# P-TK-05-2FC-A-MB_V1_1_-20171225.net
KiCad netlist of a schematic drawn in Altium Designer
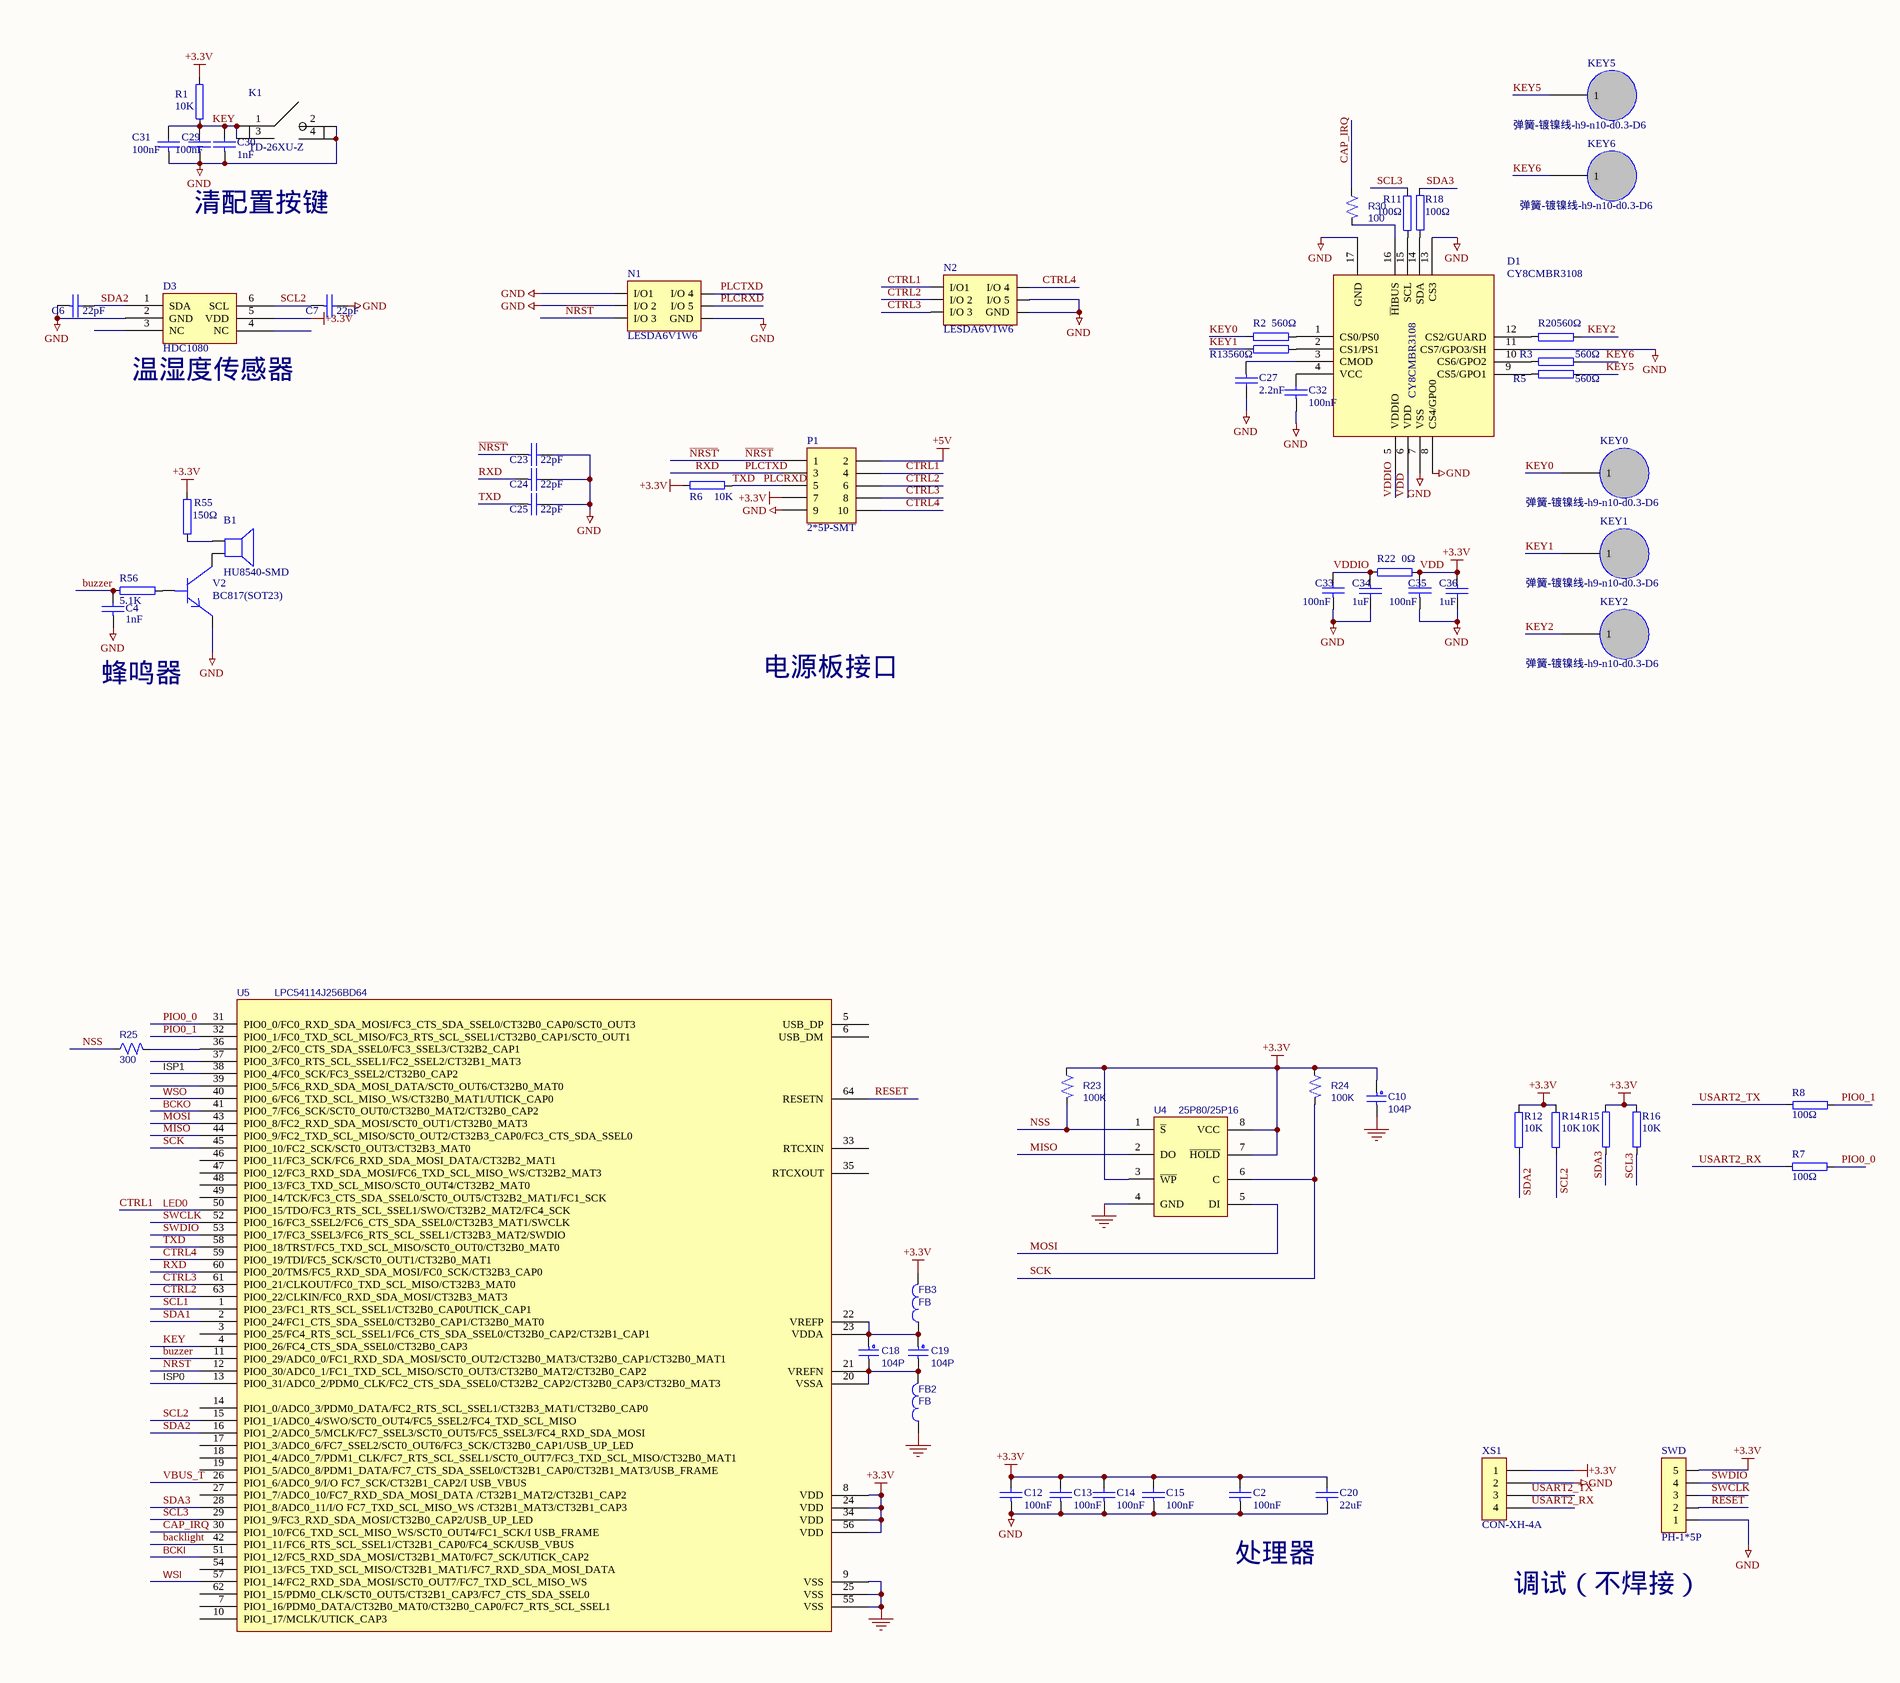
[diagram p0: P-TK-05-2FC-A-MB(V1.1)-20171225.SchDoc, left]
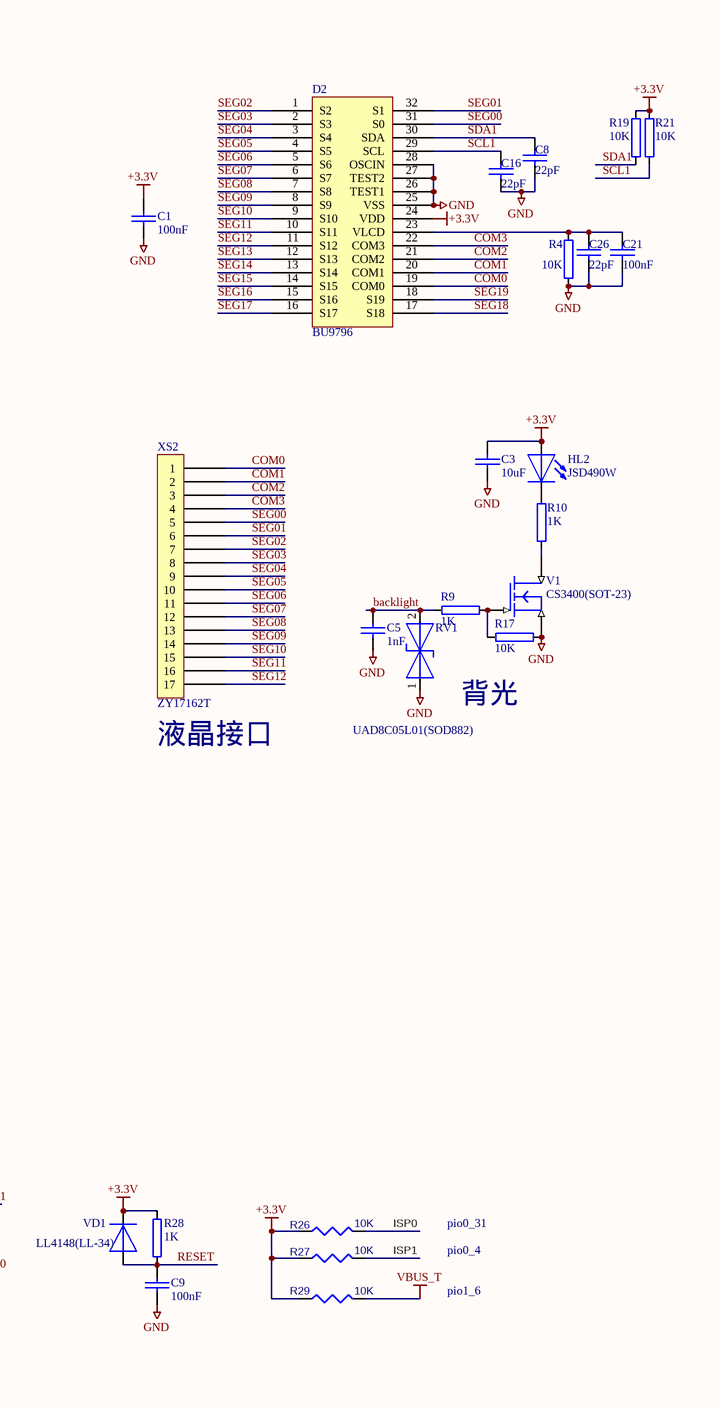
[diagram p1: P-TK-05-2FC-A-MB(V1.1)-20171225.SchDoc, right]

(export (version "E")
  (design (tool "Eeschema 10.0.6"))
  (components
    (comp (ref "B1")
      (value "HU8540-SMD")
      (footprint "HU8540")
      (description "扬声器")
      (fields (field (name "PART NUMBER") "10112020002"))
      (libsource (lib "Database_Libs1") (part "SPEAKER"))
    )
    (comp (ref "C1")
      (value "100nF")
      (footprint "C0402")
      (description "无极性电容")
      (fields (field (name "PART NUMBER") "10103020007"))
      (libsource (lib "altium-import") (part "root_1_CAP_"))
    )
    (comp (ref "C2")
      (value "100nF")
      (footprint "0603C")
      (description "无极性电容")
      (fields (field (name "PART NUMBER") "10103020007"))
      (libsource (lib "altium-import") (part "root_1_CAP_"))
    )
    (comp (ref "C3")
      (value "10uF")
      (footprint "C0603")
      (description "无极性电容")
      (fields (field (name "PART NUMBER") "10103030010"))
      (libsource (lib "altium-import") (part "root_1_CAP_"))
    )
    (comp (ref "C4")
      (value "1nF")
      (footprint "0603C")
      (description "无极性电容")
      (fields (field (name "PART NUMBER") "10103020004"))
      (libsource (lib "altium-import") (part "root_1_CAP_"))
    )
    (comp (ref "C5")
      (value "1nF")
      (footprint "0603C")
      (description "无极性电容")
      (fields (field (name "PART NUMBER") "10103020004"))
      (libsource (lib "altium-import") (part "root_1_CAP_"))
    )
    (comp (ref "C6")
      (value "22pF")
      (footprint "C0603")
      (description "无极性电容")
      (fields (field (name "PART NUMBER") "10103030023"))
      (libsource (lib "altium-import") (part "root_0_CAP_"))
    )
    (comp (ref "C7")
      (value "22pF")
      (footprint "C0603")
      (description "无极性电容")
      (fields (field (name "PART NUMBER") "10103030023"))
      (libsource (lib "altium-import") (part "root_0_CAP_"))
    )
    (comp (ref "C8")
      (value "22pF")
      (footprint "C0603")
      (description "无极性电容")
      (fields (field (name "PART NUMBER") "10103030023"))
      (libsource (lib "altium-import") (part "root_1_CAP_"))
    )
    (comp (ref "C9")
      (value "100nF")
      (footprint "0603C")
      (description "无极性电容")
      (fields (field (name "PART NUMBER") "10103020007"))
      (libsource (lib "altium-import") (part "root_1_CAP_"))
    )
    (comp (ref "C10") (value "104P") (footprint "0603C") (libsource (lib "*") (part "CAP")))
    (comp (ref "C12")
      (value "100nF")
      (footprint "0603C")
      (description "无极性电容")
      (fields (field (name "PART NUMBER") "10103020007"))
      (libsource (lib "altium-import") (part "root_1_CAP_"))
    )
    (comp (ref "C13")
      (value "100nF")
      (footprint "0603C")
      (description "无极性电容")
      (fields (field (name "PART NUMBER") "10103020007"))
      (libsource (lib "altium-import") (part "root_1_CAP_"))
    )
    (comp (ref "C14")
      (value "100nF")
      (footprint "0603C")
      (description "无极性电容")
      (fields (field (name "PART NUMBER") "10103020007"))
      (libsource (lib "altium-import") (part "root_1_CAP_"))
    )
    (comp (ref "C15")
      (value "100nF")
      (footprint "0603C")
      (description "无极性电容")
      (fields (field (name "PART NUMBER") "10103020007"))
      (libsource (lib "altium-import") (part "root_1_CAP_"))
    )
    (comp (ref "C16")
      (value "22pF")
      (footprint "C0603")
      (description "无极性电容")
      (fields (field (name "PART NUMBER") "10103030023"))
      (libsource (lib "altium-import") (part "root_1_CAP_"))
    )
    (comp (ref "C18") (value "104P") (footprint "0603C") (libsource (lib "*") (part "CAP")))
    (comp (ref "C19") (value "104P") (footprint "0603C") (libsource (lib "*") (part "CAP")))
    (comp (ref "C20")
      (value "22uF")
      (footprint "0603C")
      (description "无极性电容")
      (fields (field (name "PART NUMBER") "10103040014"))
      (libsource (lib "Database_Libs1") (part "CAP"))
    )
    (comp (ref "C21")
      (value "100nF")
      (footprint "0603C")
      (description "无极性电容")
      (fields (field (name "PART NUMBER") "10103020007"))
      (libsource (lib "altium-import") (part "root_1_CAP_"))
    )
    (comp (ref "C23")
      (value "22pF")
      (footprint "C0603")
      (description "无极性电容")
      (fields (field (name "PART NUMBER") "10103030023"))
      (libsource (lib "altium-import") (part "root_0_CAP_"))
    )
    (comp (ref "C24")
      (value "22pF")
      (footprint "C0603")
      (description "无极性电容")
      (fields (field (name "PART NUMBER") "10103030023"))
      (libsource (lib "altium-import") (part "root_0_CAP_"))
    )
    (comp (ref "C25")
      (value "22pF")
      (footprint "C0603")
      (description "无极性电容")
      (fields (field (name "PART NUMBER") "10103030023"))
      (libsource (lib "altium-import") (part "root_0_CAP_"))
    )
    (comp (ref "C26")
      (value "22pF")
      (footprint "C0603")
      (description "无极性电容")
      (fields (field (name "PART NUMBER") "10103030023"))
      (libsource (lib "altium-import") (part "root_1_CAP_"))
    )
    (comp (ref "C27")
      (value "2.2nF")
      (footprint "C0603")
      (description "无极性电容")
      (fields (field (name "PART NUMBER") "10103030025"))
      (libsource (lib "Database_Libs1") (part "CAP"))
    )
    (comp (ref "C29")
      (value "100nF")
      (footprint "0603C")
      (description "无极性电容")
      (fields (field (name "PART NUMBER") "10103020007"))
      (libsource (lib "altium-import") (part "root_1_CAP_"))
    )
    (comp (ref "C30")
      (value "1nF")
      (footprint "0603C")
      (description "无极性电容")
      (fields (field (name "PART NUMBER") "10103020004"))
      (libsource (lib "altium-import") (part "root_1_CAP_"))
    )
    (comp (ref "C31")
      (value "100nF")
      (footprint "0603C")
      (description "无极性电容")
      (fields (field (name "PART NUMBER") "10103020007"))
      (libsource (lib "altium-import") (part "root_1_CAP_"))
    )
    (comp (ref "C32")
      (value "100nF")
      (footprint "C0402")
      (description "无极性电容")
      (fields (field (name "PART NUMBER") "10103020007"))
      (libsource (lib "altium-import") (part "root_1_CAP_"))
    )
    (comp (ref "C33")
      (value "100nF")
      (footprint "C0402")
      (description "无极性电容")
      (fields (field (name "PART NUMBER") "10103020007"))
      (libsource (lib "altium-import") (part "root_1_CAP_"))
    )
    (comp (ref "C34")
      (value "1uF")
      (footprint "C0603")
      (description "无极性电容")
      (fields (field (name "PART NUMBER") "10103030008"))
      (libsource (lib "Database_Libs1") (part "CAP"))
    )
    (comp (ref "C35")
      (value "100nF")
      (footprint "C0402")
      (description "无极性电容")
      (fields (field (name "PART NUMBER") "10103020007"))
      (libsource (lib "altium-import") (part "root_1_CAP_"))
    )
    (comp (ref "C36")
      (value "1uF")
      (footprint "C0603")
      (description "无极性电容")
      (fields (field (name "PART NUMBER") "10103030008"))
      (libsource (lib "Database_Libs1") (part "CAP"))
    )
    (comp (ref "D1")
      (value "CY8CMBR3108")
      (footprint "QFN16 - 3108")
      (description "微控制器")
      (fields (field (name "PART NUMBER") "10109010004"))
      (libsource (lib "Database_Libs1") (part "CY8CMBR3108"))
    )
    (comp (ref "D2")
      (value "BU9796")
      (footprint "SSOP-32")
      (fields (field (name "PART NUMBER") "10109140005"))
      (libsource (lib "altium-import") (part "root_0_BU9796_"))
    )
    (comp (ref "D3")
      (value "HDC1080")
      (footprint "DFN6-1")
      (description "温湿度传感器")
      (fields (field (name "PART NUMBER") "10117000017"))
      (libsource (lib "Database_Libs5") (part "SI7020"))
    )
    (comp (ref "FB2") (value "FB") (footprint "0603L") (libsource (lib "*") (part "FB")))
    (comp (ref "FB3") (value "FB") (footprint "0603L") (libsource (lib "*") (part "FB")))
    (comp (ref "HL2")
      (value "JSD490W")
      (footprint "JSD490W-K")
      (description "LED-发光管类")
      (fields (field (name "PART NUMBER") "10111040012"))
      (libsource (lib "Database_Libs5") (part "LED"))
    )
    (comp (ref "K1")
      (value "TD-26XU-Z")
      (footprint "TD-26XU-Z")
      (fields (field (name "PART NUMBER") "10121000033"))
      (libsource (lib "Database_Libs5") (part "TD-26XU-Z"))
    )
    (comp (ref "KEY0")
      (value "弹簧-镀镍线-h9-n10-d0.3-D6")
      (footprint "SPRING")
      (description "弹簧")
      (fields (field (name "PART NUMBER") "10302000003"))
      (libsource (lib "Database_Libs5") (part "SPRING"))
    )
    (comp (ref "KEY1")
      (value "弹簧-镀镍线-h9-n10-d0.3-D6")
      (footprint "SPRING")
      (description "弹簧")
      (fields (field (name "PART NUMBER") "10302000003"))
      (libsource (lib "Database_Libs5") (part "SPRING"))
    )
    (comp (ref "KEY2")
      (value "弹簧-镀镍线-h9-n10-d0.3-D6")
      (footprint "SPRING")
      (description "弹簧")
      (fields (field (name "PART NUMBER") "10302000003"))
      (libsource (lib "Database_Libs5") (part "SPRING"))
    )
    (comp (ref "KEY5")
      (value "弹簧-镀镍线-h9-n10-d0.3-D6")
      (footprint "SPRING")
      (description "弹簧")
      (fields (field (name "PART NUMBER") "10302000003"))
      (libsource (lib "Database_Libs5") (part "SPRING"))
    )
    (comp (ref "KEY6")
      (value "弹簧-镀镍线-h9-n10-d0.3-D6")
      (footprint "SPRING")
      (description "弹簧")
      (fields (field (name "PART NUMBER") "10302000003"))
      (libsource (lib "Database_Libs5") (part "SPRING"))
    )
    (comp (ref "N1")
      (value "LESDA6V1W6")
      (footprint "SOT323-6L")
      (description "IC-其它类集成电路")
      (fields (field (name "PART NUMBER") "10109090005"))
      (libsource (lib "altium-import") (part "root_0_ESDA6V1_"))
    )
    (comp (ref "N2")
      (value "LESDA6V1W6")
      (footprint "SOT323-6L")
      (description "IC-其它类集成电路")
      (fields (field (name "PART NUMBER") "10109090005"))
      (libsource (lib "altium-import") (part "root_0_ESDA6V1_"))
    )
    (comp (ref "P1")
      (value "*")
      (footprint "2*5  2.54 smt")
      (fields (field (name "PART NUMBER") "10118020054"))
      (libsource (lib "Database_Libs5") (part "Header 2X5"))
    )
    (comp (ref "R1")
      (value "*")
      (footprint "0603R")
      (description "电阻")
      (fields (field (name "PART NUMBER") "10102010006"))
      (libsource (lib "altium-import") (part "root_1_RES_"))
    )
    (comp (ref "R2")
      (value "*")
      (footprint "R0603")
      (description "电阻")
      (fields (field (name "PART NUMBER") "10102020127"))
      (libsource (lib "Database_Libs1") (part "RES"))
    )
    (comp (ref "R3")
      (value "*")
      (footprint "R0603")
      (description "电阻")
      (fields (field (name "PART NUMBER") "10102020127"))
      (libsource (lib "Database_Libs1") (part "RES"))
    )
    (comp (ref "R4")
      (value "*")
      (footprint "0603R")
      (description "电阻")
      (fields (field (name "PART NUMBER") "10102010006"))
      (libsource (lib "altium-import") (part "root_1_RES_"))
    )
    (comp (ref "R5")
      (value "*")
      (footprint "R0603")
      (description "电阻")
      (fields (field (name "PART NUMBER") "10102020127"))
      (libsource (lib "Database_Libs1") (part "RES"))
    )
    (comp (ref "R6")
      (value "*")
      (footprint "0603R")
      (description "电阻")
      (fields (field (name "PART NUMBER") "10102010006"))
      (libsource (lib "altium-import") (part "root_2_RES_"))
    )
    (comp (ref "R7")
      (value "*")
      (footprint "0603R")
      (description "@")
      (fields (field (name "PART NUMBER") "10102010003"))
      (libsource (lib "altium-import") (part "root_2_RES_"))
    )
    (comp (ref "R8")
      (value "*")
      (footprint "0603R")
      (description "@")
      (fields (field (name "PART NUMBER") "10102010003"))
      (libsource (lib "altium-import") (part "root_0_RES_"))
    )
    (comp (ref "R9")
      (value "*")
      (footprint "0603R")
      (description "电阻")
      (fields (field (name "PART NUMBER") "10102010005"))
      (libsource (lib "altium-import") (part "root_0_RES_"))
    )
    (comp (ref "R10")
      (value "*")
      (footprint "R0805")
      (description "电阻")
      (fields (field (name "PART NUMBER") "10102030005"))
      (libsource (lib "Database_Libs5") (part "RES"))
    )
    (comp (ref "R11")
      (value "*")
      (footprint "0603R")
      (description "电阻")
      (fields (field (name "PART NUMBER") "10102010003"))
      (libsource (lib "altium-import") (part "root_1_RES_"))
    )
    (comp (ref "R12")
      (value "*")
      (footprint "0603R")
      (description "电阻")
      (fields (field (name "PART NUMBER") "10102010006"))
      (libsource (lib "altium-import") (part "root_1_RES_"))
    )
    (comp (ref "R13")
      (value "*")
      (footprint "R0603")
      (description "电阻")
      (fields (field (name "PART NUMBER") "10102020127"))
      (libsource (lib "Database_Libs1") (part "RES"))
    )
    (comp (ref "R14")
      (value "*")
      (footprint "0603R")
      (description "电阻")
      (fields (field (name "PART NUMBER") "10102010006"))
      (libsource (lib "altium-import") (part "root_1_RES_"))
    )
    (comp (ref "R15")
      (value "*")
      (footprint "0603R")
      (description "电阻")
      (fields (field (name "PART NUMBER") "10102010006"))
      (libsource (lib "altium-import") (part "root_3_RES_"))
    )
    (comp (ref "R16")
      (value "*")
      (footprint "0603R")
      (description "电阻")
      (fields (field (name "PART NUMBER") "10102010006"))
      (libsource (lib "altium-import") (part "root_3_RES_"))
    )
    (comp (ref "R17")
      (value "*")
      (footprint "0603R")
      (description "电阻")
      (fields (field (name "PART NUMBER") "10102010006"))
      (libsource (lib "altium-import") (part "root_2_RES_"))
    )
    (comp (ref "R18")
      (value "*")
      (footprint "0603R")
      (description "电阻")
      (fields (field (name "PART NUMBER") "10102010003"))
      (libsource (lib "altium-import") (part "root_3_RES_"))
    )
    (comp (ref "R19")
      (value "*")
      (footprint "0603R")
      (description "电阻")
      (fields (field (name "PART NUMBER") "10102010006"))
      (libsource (lib "altium-import") (part "root_3_RES_"))
    )
    (comp (ref "R20")
      (value "*")
      (footprint "R0603")
      (description "电阻")
      (fields (field (name "PART NUMBER") "10102020127"))
      (libsource (lib "Database_Libs1") (part "RES"))
    )
    (comp (ref "R21")
      (value "*")
      (footprint "0603R")
      (description "电阻")
      (fields (field (name "PART NUMBER") "10102010006"))
      (libsource (lib "altium-import") (part "root_3_RES_"))
    )
    (comp (ref "R22")
      (value "*")
      (footprint "R0603")
      (description "电阻")
      (fields (field (name "PART NUMBER") "10102020001"))
      (libsource (lib "Database_Libs1") (part "RES"))
    )
    (comp (ref "R23") (value "100K") (footprint "0603R") (libsource (lib "*") (part "RES3")))
    (comp (ref "R24") (value "100K") (footprint "0603R") (libsource (lib "*") (part "RES3")))
    (comp (ref "R25") (value "300") (footprint "0603R") (libsource (lib "*") (part "RES3")))
    (comp (ref "R26") (value "10K") (footprint "0603R") (libsource (lib "*") (part "RES1")))
    (comp (ref "R27") (value "10K") (footprint "0603R") (libsource (lib "*") (part "RES1")))
    (comp (ref "R28")
      (value "*")
      (footprint "0603R")
      (description "电阻")
      (fields (field (name "PART NUMBER") "10102010005"))
      (libsource (lib "altium-import") (part "root_3_RES_"))
    )
    (comp (ref "R29") (value "10K") (footprint "0603R") (libsource (lib "*") (part "RES1")))
    (comp (ref "R30") (value "100") (footprint "0603R") (libsource (lib "*") (part "RES3")))
    (comp (ref "R55")
      (value "*")
      (footprint "R0603")
      (description "电阻")
      (fields (field (name "PART NUMBER") "10102020026"))
      (libsource (lib "Database_Libs1") (part "RES"))
    )
    (comp (ref "R56")
      (value "*")
      (footprint "R0603")
      (description "电阻")
      (fields (field (name "PART NUMBER") "10102020116"))
      (libsource (lib "Database_Libs1") (part "RES"))
    )
    (comp (ref "RV1")
      (value "UAD8C05L01(SOD882)")
      (footprint "SOD-882")
      (description "TVS-TVS管")
      (fields (field (name "PART NUMBER") "10105050017"))
      (libsource (lib "Database_Libs1") (part "TVS"))
    )
    (comp (ref "SWD")
      (value "PH-1*5P")
      (footprint "SIP5")
      (description "@")
      (fields (field (name "PART NUMBER") "10118010013"))
      (libsource (lib "altium-import") (part "root_2_CON5_"))
    )
    (comp (ref "U4") (value "25P80/25P16") (footprint "SO8W") (libsource (lib "*") (part "M25PXX(8)")))
    (comp (ref "U5")
      (value "LPC54114J256BD64")
      (footprint "LQFP64")
      (libsource (lib "*") (part "LPC5411X_LQFP64"))
    )
    (comp (ref "V1")
      (value "CS3400(SOT-23)")
      (footprint "SOT-23-MOS")
      (description "N沟道绝缘栅场效应管_增强型")
      (fields (field (name "PART NUMBER") "10107050002"))
      (libsource (lib "altium-import") (part "root_0_MOSFET_N_"))
    )
    (comp (ref "V2")
      (value "BC817(SOT23)")
      (footprint "SOT-23")
      (description "NPN三极管")
      (fields (field (name "PART NUMBER") "10107010003"))
      (libsource (lib "Database_Libs1") (part "NPN"))
    )
    (comp (ref "VD1")
      (value "LL4148(LL-34)")
      (footprint "LL-34")
      (description "DIODE-整流二极管类")
      (fields (field (name "PART NUMBER") "10105040022"))
      (libsource (lib "altium-import") (part "root_1_DIODE_"))
    )
    (comp (ref "XS1")
      (value "CON-XH-4A")
      (footprint "SIP4")
      (description "@")
      (fields (field (name "PART NUMBER") "10118030031"))
      (libsource (lib "altium-import") (part "root_2_mirrored_CON4_"))
    )
    (comp (ref "XS2")
      (value "ZY17162T")
      (footprint "ZY17162T")
      (fields (field (name "PART NUMBER") "10116020006"))
      (libsource (lib "Database_Libs5") (part "CON17"))
    )
  )
  (nets
    (net (code "1") (name "+3.3V") (class "Default")
      (node (ref "C1") (pin "2") (pintype "passive"))
      (node (ref "C10") (pin "1") (pinfunction "1_1") (pintype "passive"))
      (node (ref "C12") (pin "2") (pintype "passive"))
      (node (ref "C13") (pin "2") (pintype "passive"))
      (node (ref "C14") (pin "2") (pintype "passive"))
      (node (ref "C15") (pin "2") (pintype "passive"))
      (node (ref "C2") (pin "2") (pintype "passive"))
      (node (ref "C20") (pin "2") (pintype "passive"))
      (node (ref "C3") (pin "2") (pintype "passive"))
      (node (ref "C35") (pin "2") (pintype "passive"))
      (node (ref "C36") (pin "1") (pintype "passive"))
      (node (ref "D1") (pin "6") (pinfunction "VDD_6") (pintype "passive"))
      (node (ref "D2") (pin "24") (pinfunction "VDD_24") (pintype "passive"))
      (node (ref "D3") (pin "5") (pinfunction "VDD_5") (pintype "passive"))
      (node (ref "FB3") (pin "2") (pinfunction "2_2") (pintype "passive"))
      (node (ref "HL2") (pin "A") (pintype "passive"))
      (node (ref "P1") (pin "7") (pinfunction "7_7") (pintype "passive"))
      (node (ref "R1") (pin "2") (pintype "passive"))
      (node (ref "R12") (pin "2") (pintype "passive"))
      (node (ref "R14") (pin "2") (pintype "passive"))
      (node (ref "R15") (pin "1") (pintype "passive"))
      (node (ref "R16") (pin "1") (pintype "passive"))
      (node (ref "R19") (pin "1") (pintype "passive"))
      (node (ref "R21") (pin "1") (pintype "passive"))
      (node (ref "R22") (pin "1") (pintype "passive"))
      (node (ref "R23") (pin "1") (pinfunction "1_1") (pintype "passive"))
      (node (ref "R24") (pin "1") (pinfunction "1_1") (pintype "passive"))
      (node (ref "R26") (pin "1") (pinfunction "1_1") (pintype "passive"))
      (node (ref "R27") (pin "1") (pinfunction "1_1") (pintype "passive"))
      (node (ref "R28") (pin "1") (pintype "passive"))
      (node (ref "R29") (pin "1") (pinfunction "1_1") (pintype "passive"))
      (node (ref "R55") (pin "2") (pintype "passive"))
      (node (ref "R6") (pin "2") (pintype "passive"))
      (node (ref "SWD") (pin "5") (pinfunction "5_5") (pintype "power_in"))
      (node (ref "U4") (pin "3") (pinfunction "~{WP}_3") (pintype "passive"))
      (node (ref "U4") (pin "7") (pinfunction "~{HOLD}_7") (pintype "passive"))
      (node (ref "U4") (pin "8") (pinfunction "VCC_8") (pintype "passive"))
      (node (ref "U5") (pin "24") (pinfunction "VDD_24") (pintype "passive"))
      (node (ref "U5") (pin "34") (pinfunction "VDD_34") (pintype "passive"))
      (node (ref "U5") (pin "56") (pinfunction "VDD_56") (pintype "passive"))
      (node (ref "U5") (pin "8") (pinfunction "VDD_8") (pintype "passive"))
      (node (ref "VD1") (pin "K") (pintype "passive"))
      (node (ref "XS1") (pin "1") (pinfunction "1_1") (pintype "passive"))
    )
    (net (code "2") (name "+5V") (class "Default")
      (node (ref "P1") (pin "2") (pinfunction "2_2") (pintype "passive"))
    )
    (net (code "4") (name "/BCKI") (class "Default")
      (node (ref "U5") (pin "51") (pinfunction "PIO1_12/FC5_RXD_SDA_MOSI/CT32B1_MAT0/FC7_SCK/UTICK_CAP2_51") (pintype "passive"))
    )
    (net (code "5") (name "/BCKO") (class "Default")
      (node (ref "U5") (pin "41") (pinfunction "PIO0_7/FC6_SCK/SCT0_OUT0/CT32B0_MAT2/CT32B0_CAP2_41") (pintype "passive"))
    )
    (net (code "6") (name "/CAP_IRQ") (class "Default")
      (node (ref "R30") (pin "1") (pinfunction "1_1") (pintype "passive"))
      (node (ref "U5") (pin "30") (pinfunction "PIO1_10/FC6_TXD_SCL_MISO_WS/SCT0_OUT4/FC1_SCK/I_USB_FRAME_30") (pintype "passive"))
    )
    (net (code "7") (name "/COM0") (class "Default")
      (node (ref "D2") (pin "19") (pinfunction "COM0_19") (pintype "passive"))
      (node (ref "XS2") (pin "1") (pinfunction "1_1") (pintype "passive"))
    )
    (net (code "8") (name "/COM1") (class "Default")
      (node (ref "D2") (pin "20") (pinfunction "COM1_20") (pintype "passive"))
      (node (ref "XS2") (pin "2") (pinfunction "2_2") (pintype "passive"))
    )
    (net (code "9") (name "/COM2") (class "Default")
      (node (ref "D2") (pin "21") (pinfunction "COM2_21") (pintype "passive"))
      (node (ref "XS2") (pin "3") (pinfunction "3_3") (pintype "passive"))
    )
    (net (code "10") (name "/COM3") (class "Default")
      (node (ref "D2") (pin "22") (pinfunction "COM3_22") (pintype "passive"))
      (node (ref "XS2") (pin "4") (pinfunction "4_4") (pintype "passive"))
    )
    (net (code "11") (name "/CTRL1") (class "Default")
      (node (ref "N2") (pin "1") (pinfunction "I/O1_1") (pintype "passive"))
      (node (ref "P1") (pin "4") (pinfunction "4_4") (pintype "passive"))
      (node (ref "U5") (pin "50") (pinfunction "PIO0_15/TDO/FC3_RTS_SCL_SSEL1/SWO/CT32B2_MAT2/FC4_SCK_50") (pintype "passive"))
    )
    (net (code "12") (name "/CTRL2") (class "Default")
      (node (ref "N2") (pin "3") (pinfunction "I/O_2_3") (pintype "passive"))
      (node (ref "P1") (pin "6") (pinfunction "6_6") (pintype "passive"))
      (node (ref "U5") (pin "63") (pinfunction "PIO0_22/CLKIN/FC0_RXD_SDA_MOSI/CT32B3_MAT3_63") (pintype "passive"))
    )
    (net (code "13") (name "/CTRL3") (class "Default")
      (node (ref "N2") (pin "4") (pinfunction "I/O_3_4") (pintype "passive"))
      (node (ref "P1") (pin "8") (pinfunction "8_8") (pintype "passive"))
      (node (ref "U5") (pin "61") (pinfunction "PIO0_21/CLKOUT/FC0_TXD_SCL_MISO/CT32B3_MAT0_61") (pintype "passive"))
    )
    (net (code "14") (name "/CTRL4") (class "Default")
      (node (ref "N2") (pin "5") (pinfunction "I/O_4_5") (pintype "passive"))
      (node (ref "P1") (pin "10") (pinfunction "10_10") (pintype "passive"))
      (node (ref "U5") (pin "59") (pinfunction "PIO0_19/TDI/FC5_SCK/SCT0_OUT1/CT32B0_MAT1_59") (pintype "passive"))
    )
    (net (code "15") (name "/ISP0") (class "Default")
      (node (ref "R26") (pin "2") (pinfunction "2_2") (pintype "passive"))
      (node (ref "U5") (pin "13") (pinfunction "PIO0_31/ADC0_2/PDM0_CLK/FC2_CTS_SDA_SSEL0/CT32B2_CAP2/CT32B0_CAP3/CT32B0_MAT3_13") (pintype "passive"))
    )
    (net (code "16") (name "/ISP1") (class "Default")
      (node (ref "R27") (pin "2") (pinfunction "2_2") (pintype "passive"))
      (node (ref "U5") (pin "38") (pinfunction "PIO0_4/FC0_SCK/FC3_SSEL2/CT32B0_CAP2_38") (pintype "passive"))
    )
    (net (code "17") (name "/KEY") (class "Default")
      (node (ref "C29") (pin "2") (pintype "passive"))
      (node (ref "C30") (pin "2") (pintype "passive"))
      (node (ref "C31") (pin "2") (pintype "passive"))
      (node (ref "K1") (pin "1") (pinfunction "1_1") (pintype "passive"))
      (node (ref "K1") (pin "3") (pinfunction "3_3") (pintype "passive"))
      (node (ref "R1") (pin "1") (pintype "passive"))
      (node (ref "U5") (pin "4") (pinfunction "PIO0_26/FC4_CTS_SDA_SSEL0/CT32B0_CAP3_4") (pintype "passive"))
    )
    (net (code "18") (name "/KEY0") (class "Default")
      (node (ref "KEY0") (pin "1") (pinfunction "1_1") (pintype "passive"))
      (node (ref "R2") (pin "2") (pintype "passive"))
    )
    (net (code "19") (name "/KEY1") (class "Default")
      (node (ref "KEY1") (pin "1") (pinfunction "1_1") (pintype "passive"))
      (node (ref "R13") (pin "2") (pintype "passive"))
    )
    (net (code "20") (name "/KEY2") (class "Default")
      (node (ref "KEY2") (pin "1") (pinfunction "1_1") (pintype "passive"))
      (node (ref "R20") (pin "2") (pintype "passive"))
    )
    (net (code "21") (name "/KEY5") (class "Default")
      (node (ref "KEY5") (pin "1") (pinfunction "1_1") (pintype "passive"))
      (node (ref "R5") (pin "2") (pintype "passive"))
    )
    (net (code "22") (name "/KEY6") (class "Default")
      (node (ref "KEY6") (pin "1") (pinfunction "1_1") (pintype "passive"))
      (node (ref "R3") (pin "2") (pintype "passive"))
    )
    (net (code "23") (name "/MISO") (class "Default")
      (node (ref "U4") (pin "2") (pinfunction "DO_2") (pintype "passive"))
      (node (ref "U5") (pin "44") (pinfunction "PIO0_9/FC2_TXD_SCL_MISO/SCT0_OUT2/CT32B3_CAP0/FC3_CTS_SDA_SSEL0_44") (pintype "passive"))
    )
    (net (code "24") (name "/MOSI") (class "Default")
      (node (ref "U4") (pin "5") (pinfunction "DI_5") (pintype "passive"))
      (node (ref "U5") (pin "43") (pinfunction "PIO0_8/FC2_RXD_SDA_MOSI/SCT0_OUT1/CT32B0_MAT3_43") (pintype "passive"))
    )
    (net (code "25") (name "/NSS") (class "Default")
      (node (ref "R23") (pin "2") (pinfunction "2_2") (pintype "passive"))
      (node (ref "R25") (pin "1") (pinfunction "1_1") (pintype "passive"))
      (node (ref "U4") (pin "1") (pinfunction "~{S}_1") (pintype "passive"))
    )
    (net (code "26") (name "/PIO0_0") (class "Default")
      (node (ref "R7") (pin "1") (pintype "passive"))
      (node (ref "U5") (pin "31") (pinfunction "PIO0_0/FC0_RXD_SDA_MOSI/FC3_CTS_SDA_SSEL0/CT32B0_CAP0/SCT0_OUT3_31") (pintype "passive"))
    )
    (net (code "27") (name "/PIO0_1") (class "Default")
      (node (ref "R8") (pin "2") (pintype "passive"))
      (node (ref "U5") (pin "32") (pinfunction "PIO0_1/FC0_TXD_SCL_MISO/FC3_RTS_SCL_SSEL1/CT32B0_CAP1/SCT0_OUT1_32") (pintype "passive"))
    )
    (net (code "28") (name "/PLCRXD") (class "Default")
      (node (ref "C25") (pin "1") (pintype "passive"))
      (node (ref "N1") (pin "6") (pinfunction "I/O_5_6") (pintype "passive"))
      (node (ref "P1") (pin "5") (pinfunction "5_5") (pintype "passive"))
      (node (ref "R6") (pin "1") (pintype "passive"))
      (node (ref "U5") (pin "58") (pinfunction "PIO0_18/TRST/FC5_TXD_SCL_MISO/SCT0_OUT0/CT32B0_MAT0_58") (pintype "passive"))
    )
    (net (code "29") (name "/PLCTXD") (class "Default")
      (node (ref "C24") (pin "1") (pintype "passive"))
      (node (ref "N1") (pin "5") (pinfunction "I/O_4_5") (pintype "passive"))
      (node (ref "P1") (pin "3") (pinfunction "3_3") (pintype "passive"))
      (node (ref "U5") (pin "60") (pinfunction "PIO0_20/TMS/FC5_RXD_SDA_MOSI/FC0_SCK/CT32B3_CAP0_60") (pintype "passive"))
    )
    (net (code "30") (name "/RESET") (class "Default")
      (node (ref "C9") (pin "2") (pintype "passive"))
      (node (ref "R28") (pin "2") (pintype "passive"))
      (node (ref "SWD") (pin "2") (pinfunction "2_2") (pintype "passive"))
      (node (ref "U5") (pin "64") (pinfunction "RESETN_64") (pintype "passive"))
      (node (ref "VD1") (pin "A") (pintype "passive"))
    )
    (net (code "31") (name "/SCK") (class "Default")
      (node (ref "R24") (pin "2") (pinfunction "2_2") (pintype "passive"))
      (node (ref "U4") (pin "6") (pinfunction "C_6") (pintype "passive"))
      (node (ref "U5") (pin "45") (pinfunction "PIO0_10/FC2_SCK/SCT0_OUT3/CT32B3_MAT0_45") (pintype "passive"))
    )
    (net (code "32") (name "/SCL1") (class "Default")
      (node (ref "C16") (pin "2") (pintype "passive"))
      (node (ref "D2") (pin "29") (pinfunction "SCL_29") (pintype "passive"))
      (node (ref "R21") (pin "2") (pintype "passive"))
      (node (ref "U5") (pin "1") (pinfunction "PIO0_23/FC1_RTS_SCL_SSEL1/CT32B0_CAP0UTICK_CAP1_1") (pintype "passive"))
    )
    (net (code "33") (name "/SCL2") (class "Default")
      (node (ref "C7") (pin "1") (pintype "passive"))
      (node (ref "D3") (pin "6") (pinfunction "SCL_6") (pintype "passive"))
      (node (ref "R14") (pin "1") (pintype "passive"))
      (node (ref "U5") (pin "15") (pinfunction "PIO1_1/ADC0_4/SWO/SCT0_OUT4/FC5_SSEL2/FC4_TXD_SCL_MISO_15") (pintype "passive"))
    )
    (net (code "34") (name "/SCL3") (class "Default")
      (node (ref "R11") (pin "2") (pintype "passive"))
      (node (ref "R16") (pin "2") (pintype "passive"))
      (node (ref "U5") (pin "29") (pinfunction "PIO1_9/FC3_RXD_SDA_MOSI/CT32B0_CAP2/USB_UP_LED_29") (pintype "passive"))
    )
    (net (code "35") (name "/SDA1") (class "Default")
      (node (ref "C8") (pin "2") (pintype "passive"))
      (node (ref "D2") (pin "30") (pinfunction "SDA_30") (pintype "passive"))
      (node (ref "R19") (pin "2") (pintype "passive"))
      (node (ref "U5") (pin "2") (pinfunction "PIO0_24/FC1_CTS_SDA_SSEL0/CT32B0_CAP1/CT32B0_MAT0_2") (pintype "passive"))
    )
    (net (code "36") (name "/SDA2") (class "Default")
      (node (ref "C6") (pin "2") (pintype "passive"))
      (node (ref "D3") (pin "1") (pinfunction "SDA_1") (pintype "passive"))
      (node (ref "R12") (pin "1") (pintype "passive"))
      (node (ref "U5") (pin "16") (pinfunction "PIO1_2/ADC0_5/MCLK/FC7_SSEL3/SCT0_OUT5/FC5_SSEL3/FC4_RXD_SDA_MOSI_16") (pintype "passive"))
    )
    (net (code "37") (name "/SDA3") (class "Default")
      (node (ref "R15") (pin "2") (pintype "passive"))
      (node (ref "R18") (pin "1") (pintype "passive"))
      (node (ref "U5") (pin "28") (pinfunction "PIO1_8/ADC0_11/I/O_FC7_TXD_SCL_MISO_WS_/CT32B1_MAT3/CT32B1_CAP3_28") (pintype "passive"))
    )
    (net (code "38") (name "/SEG00") (class "Default")
      (node (ref "D2") (pin "31") (pinfunction "S0_31") (pintype "passive"))
      (node (ref "XS2") (pin "5") (pinfunction "5_5") (pintype "passive"))
    )
    (net (code "39") (name "/SEG01") (class "Default")
      (node (ref "D2") (pin "32") (pinfunction "S1_32") (pintype "passive"))
      (node (ref "XS2") (pin "6") (pinfunction "6_6") (pintype "passive"))
    )
    (net (code "40") (name "/SEG02") (class "Default")
      (node (ref "D2") (pin "1") (pinfunction "S2_1") (pintype "passive"))
      (node (ref "XS2") (pin "7") (pinfunction "7_7") (pintype "passive"))
    )
    (net (code "41") (name "/SEG03") (class "Default")
      (node (ref "D2") (pin "2") (pinfunction "S3_2") (pintype "passive"))
      (node (ref "XS2") (pin "8") (pinfunction "8_8") (pintype "passive"))
    )
    (net (code "42") (name "/SEG04") (class "Default")
      (node (ref "D2") (pin "3") (pinfunction "S4_3") (pintype "passive"))
      (node (ref "XS2") (pin "9") (pinfunction "9_9") (pintype "passive"))
    )
    (net (code "43") (name "/SEG05") (class "Default")
      (node (ref "D2") (pin "4") (pinfunction "S5_4") (pintype "passive"))
      (node (ref "XS2") (pin "10") (pinfunction "10_10") (pintype "passive"))
    )
    (net (code "44") (name "/SEG06") (class "Default")
      (node (ref "D2") (pin "5") (pinfunction "S6_5") (pintype "passive"))
      (node (ref "XS2") (pin "11") (pinfunction "11_11") (pintype "passive"))
    )
    (net (code "45") (name "/SEG07") (class "Default")
      (node (ref "D2") (pin "6") (pinfunction "S7_6") (pintype "passive"))
      (node (ref "XS2") (pin "12") (pinfunction "12_12") (pintype "passive"))
    )
    (net (code "46") (name "/SEG08") (class "Default")
      (node (ref "D2") (pin "7") (pinfunction "S8_7") (pintype "passive"))
      (node (ref "XS2") (pin "13") (pinfunction "13_13") (pintype "passive"))
    )
    (net (code "47") (name "/SEG09") (class "Default")
      (node (ref "D2") (pin "8") (pinfunction "S9_8") (pintype "passive"))
      (node (ref "XS2") (pin "14") (pinfunction "14_14") (pintype "passive"))
    )
    (net (code "48") (name "/SEG10") (class "Default")
      (node (ref "D2") (pin "9") (pinfunction "S10_9") (pintype "passive"))
      (node (ref "XS2") (pin "15") (pinfunction "15_15") (pintype "passive"))
    )
    (net (code "49") (name "/SEG11") (class "Default")
      (node (ref "D2") (pin "10") (pinfunction "S11_10") (pintype "passive"))
      (node (ref "XS2") (pin "16") (pinfunction "16_16") (pintype "passive"))
    )
    (net (code "50") (name "/SEG12") (class "Default")
      (node (ref "D2") (pin "11") (pinfunction "S12_11") (pintype "passive"))
      (node (ref "XS2") (pin "17") (pinfunction "17_17") (pintype "passive"))
    )
    (net (code "51") (name "/SEG13") (class "Default")
      (node (ref "D2") (pin "12") (pinfunction "S13_12") (pintype "passive"))
    )
    (net (code "52") (name "/SEG14") (class "Default")
      (node (ref "D2") (pin "13") (pinfunction "S14_13") (pintype "passive"))
    )
    (net (code "53") (name "/SEG15") (class "Default")
      (node (ref "D2") (pin "14") (pinfunction "S15_14") (pintype "passive"))
    )
    (net (code "54") (name "/SEG16") (class "Default")
      (node (ref "D2") (pin "15") (pinfunction "S16_15") (pintype "passive"))
    )
    (net (code "55") (name "/SEG17") (class "Default")
      (node (ref "D2") (pin "16") (pinfunction "S17_16") (pintype "passive"))
    )
    (net (code "56") (name "/SEG18") (class "Default")
      (node (ref "D2") (pin "17") (pinfunction "S18_17") (pintype "passive"))
    )
    (net (code "57") (name "/SEG19") (class "Default")
      (node (ref "D2") (pin "18") (pinfunction "S19_18") (pintype "passive"))
    )
    (net (code "58") (name "/SWCLK") (class "Default")
      (node (ref "SWD") (pin "3") (pinfunction "3_3") (pintype "passive"))
      (node (ref "U5") (pin "52") (pinfunction "PIO0_16/FC3_SSEL2/FC6_CTS_SDA_SSEL0/CT32B3_MAT1/SWCLK_52") (pintype "passive"))
    )
    (net (code "59") (name "/SWDIO") (class "Default")
      (node (ref "SWD") (pin "4") (pinfunction "4_4") (pintype "power_in"))
      (node (ref "U5") (pin "53") (pinfunction "PIO0_17/FC3_SSEL3/FC6_RTS_SCL_SSEL1/CT32B3_MAT2/SWDIO_53") (pintype "passive"))
    )
    (net (code "60") (name "/USART2_RX") (class "Default")
      (node (ref "R7") (pin "2") (pintype "passive"))
      (node (ref "XS1") (pin "4") (pinfunction "4_4") (pintype "passive"))
    )
    (net (code "61") (name "/USART2_TX") (class "Default")
      (node (ref "R8") (pin "1") (pintype "passive"))
      (node (ref "XS1") (pin "3") (pinfunction "3_3") (pintype "passive"))
    )
    (net (code "62") (name "/VDDIO") (class "Default")
      (node (ref "C33") (pin "2") (pintype "passive"))
      (node (ref "C34") (pin "1") (pintype "passive"))
      (node (ref "D1") (pin "5") (pinfunction "VDDIO_5") (pintype "passive"))
      (node (ref "R22") (pin "2") (pintype "passive"))
    )
    (net (code "63") (name "/WSI") (class "Default")
      (node (ref "U5") (pin "57") (pinfunction "PIO1_14/FC2_RXD_SDA_MOSI/SCT0_OUT7/FC7_TXD_SCL_MISO_WS_57") (pintype "passive"))
    )
    (net (code "64") (name "/WSO") (class "Default")
      (node (ref "U5") (pin "40") (pinfunction "PIO0_6/FC6_TXD_SCL_MISO_WS/CT32B0_MAT1/UTICK_CAP0_40") (pintype "passive"))
    )
    (net (code "65") (name "/backlight") (class "Default")
      (node (ref "C5") (pin "2") (pintype "passive"))
      (node (ref "R9") (pin "1") (pintype "passive"))
      (node (ref "RV1") (pin "2") (pintype "passive"))
      (node (ref "U5") (pin "42") (pinfunction "PIO1_11/FC6_RTS_SCL_SSEL1/CT32B1_CAP0/FC4_SCK/USB_VBUS_42") (pintype "passive"))
    )
    (net (code "66") (name "/buzzer") (class "Default")
      (node (ref "C4") (pin "2") (pintype "passive"))
      (node (ref "R56") (pin "2") (pintype "passive"))
      (node (ref "U5") (pin "11") (pinfunction "PIO0_29/ADC0_0/FC1_RXD_SDA_MOSI/SCT0_OUT2/CT32B0_MAT3/CT32B0_CAP1/CT32B0_MAT1_11") (pintype "passive"))
    )
    (net (code "67") (name "/~{NRST}") (class "Default")
      (node (ref "C23") (pin "1") (pintype "passive"))
      (node (ref "N1") (pin "4") (pinfunction "I/O_3_4") (pintype "passive"))
      (node (ref "P1") (pin "1") (pinfunction "1_1") (pintype "passive"))
      (node (ref "U5") (pin "12") (pinfunction "PIO0_30/ADC0_1/FC1_TXD_SCL_MISO/SCT0_OUT3/CT32B0_MAT2/CT32B0_CAP2_12") (pintype "passive"))
    )
    (net (code "68") (name "GND") (class "Default")
      (node (ref "C1") (pin "1") (pintype "passive"))
      (node (ref "C10") (pin "2") (pinfunction "2_2") (pintype "passive"))
      (node (ref "C12") (pin "1") (pintype "passive"))
      (node (ref "C13") (pin "1") (pintype "passive"))
      (node (ref "C14") (pin "1") (pintype "passive"))
      (node (ref "C15") (pin "1") (pintype "passive"))
      (node (ref "C16") (pin "1") (pintype "passive"))
      (node (ref "C2") (pin "1") (pintype "passive"))
      (node (ref "C20") (pin "1") (pintype "passive"))
      (node (ref "C21") (pin "1") (pintype "passive"))
      (node (ref "C23") (pin "2") (pintype "passive"))
      (node (ref "C24") (pin "2") (pintype "passive"))
      (node (ref "C25") (pin "2") (pintype "passive"))
      (node (ref "C26") (pin "1") (pintype "passive"))
      (node (ref "C27") (pin "2") (pintype "passive"))
      (node (ref "C29") (pin "1") (pintype "passive"))
      (node (ref "C3") (pin "1") (pintype "passive"))
      (node (ref "C30") (pin "1") (pintype "passive"))
      (node (ref "C31") (pin "1") (pintype "passive"))
      (node (ref "C32") (pin "1") (pintype "passive"))
      (node (ref "C33") (pin "1") (pintype "passive"))
      (node (ref "C34") (pin "2") (pintype "passive"))
      (node (ref "C35") (pin "1") (pintype "passive"))
      (node (ref "C36") (pin "2") (pintype "passive"))
      (node (ref "C4") (pin "1") (pintype "passive"))
      (node (ref "C5") (pin "1") (pintype "passive"))
      (node (ref "C6") (pin "1") (pintype "passive"))
      (node (ref "C7") (pin "2") (pintype "passive"))
      (node (ref "C8") (pin "1") (pintype "passive"))
      (node (ref "C9") (pin "1") (pintype "passive"))
      (node (ref "D1") (pin "11") (pinfunction "CS7/GPO3/SH_11") (pintype "passive"))
      (node (ref "D1") (pin "13") (pinfunction "CS3_13") (pintype "passive"))
      (node (ref "D1") (pin "17") (pinfunction "GND_17") (pintype "passive"))
      (node (ref "D1") (pin "7") (pinfunction "VSS_7") (pintype "passive"))
      (node (ref "D1") (pin "8") (pinfunction "CS4/GPO0_8") (pintype "passive"))
      (node (ref "D2") (pin "25") (pinfunction "VSS_25") (pintype "passive"))
      (node (ref "D2") (pin "26") (pinfunction "TEST1_26") (pintype "passive"))
      (node (ref "D2") (pin "27") (pinfunction "TEST2_27") (pintype "passive"))
      (node (ref "D2") (pin "28") (pinfunction "OSCIN_28") (pintype "passive"))
      (node (ref "D3") (pin "2") (pinfunction "GND_2") (pintype "passive"))
      (node (ref "FB2") (pin "1") (pinfunction "1_1") (pintype "passive"))
      (node (ref "K1") (pin "2") (pinfunction "2_2") (pintype "passive"))
      (node (ref "K1") (pin "4") (pinfunction "4_4") (pintype "passive"))
      (node (ref "N1") (pin "1") (pinfunction "I/O1_1") (pintype "passive"))
      (node (ref "N1") (pin "2") (pinfunction "GND_2") (pintype "passive"))
      (node (ref "N1") (pin "3") (pinfunction "I/O_2_3") (pintype "passive"))
      (node (ref "N2") (pin "2") (pinfunction "GND_2") (pintype "passive"))
      (node (ref "N2") (pin "6") (pinfunction "I/O_5_6") (pintype "passive"))
      (node (ref "P1") (pin "9") (pinfunction "9_9") (pintype "passive"))
      (node (ref "R17") (pin "1") (pintype "passive"))
      (node (ref "R4") (pin "1") (pintype "passive"))
      (node (ref "RV1") (pin "1") (pintype "passive"))
      (node (ref "SWD") (pin "1") (pinfunction "1_1") (pintype "passive"))
      (node (ref "U4") (pin "4") (pinfunction "GND_4") (pintype "passive"))
      (node (ref "U5") (pin "25") (pinfunction "VSS_25") (pintype "passive"))
      (node (ref "U5") (pin "55") (pinfunction "VSS_55") (pintype "passive"))
      (node (ref "U5") (pin "9") (pinfunction "VSS_9") (pintype "passive"))
      (node (ref "V1") (pin "S") (pinfunction "S_S") (pintype "input"))
      (node (ref "V2") (pin "E") (pintype "passive"))
      (node (ref "XS1") (pin "2") (pinfunction "2_2") (pintype "passive"))
    )
    (net (code "69") (name "Net-(B1-Pad1)") (class "Default")
      (node (ref "B1") (pin "1") (pintype "passive"))
      (node (ref "R55") (pin "1") (pintype "passive"))
    )
    (net (code "70") (name "Net-(B1-Pad2)") (class "Default")
      (node (ref "B1") (pin "2") (pintype "passive"))
      (node (ref "V2") (pin "C") (pintype "passive"))
    )
    (net (code "71") (name "Net-(D1-CMOD)") (class "Default")
      (node (ref "C27") (pin "1") (pintype "passive"))
      (node (ref "D1") (pin "3") (pinfunction "CMOD_3") (pintype "passive"))
    )
    (net (code "72") (name "Net-(D1-CS0{slash}PS0)") (class "Default")
      (node (ref "D1") (pin "1") (pinfunction "CS0/PS0_1") (pintype "passive"))
      (node (ref "R2") (pin "1") (pintype "passive"))
    )
    (net (code "73") (name "Net-(D1-CS1{slash}PS1)") (class "Default")
      (node (ref "D1") (pin "2") (pinfunction "CS1/PS1_2") (pintype "passive"))
      (node (ref "R13") (pin "1") (pintype "passive"))
    )
    (net (code "74") (name "Net-(D1-CS2{slash}GUARD)") (class "Default")
      (node (ref "D1") (pin "12") (pinfunction "CS2/GUARD_12") (pintype "passive"))
      (node (ref "R20") (pin "1") (pintype "passive"))
    )
    (net (code "75") (name "Net-(D1-CS5{slash}GPO1)") (class "Default")
      (node (ref "D1") (pin "9") (pinfunction "CS5/GPO1_9") (pintype "passive"))
      (node (ref "R5") (pin "1") (pintype "passive"))
    )
    (net (code "76") (name "Net-(D1-CS6{slash}GPO2)") (class "Default")
      (node (ref "D1") (pin "10") (pinfunction "CS6/GPO2_10") (pintype "passive"))
      (node (ref "R3") (pin "1") (pintype "passive"))
    )
    (net (code "77") (name "Net-(D1-SCL)") (class "Default")
      (node (ref "D1") (pin "15") (pinfunction "SCL_15") (pintype "passive"))
      (node (ref "R11") (pin "1") (pintype "passive"))
    )
    (net (code "78") (name "Net-(D1-SDA)") (class "Default")
      (node (ref "D1") (pin "14") (pinfunction "SDA_14") (pintype "passive"))
      (node (ref "R18") (pin "2") (pintype "passive"))
    )
    (net (code "79") (name "Net-(D1-VCC)") (class "Default")
      (node (ref "C32") (pin "2") (pintype "passive"))
      (node (ref "D1") (pin "4") (pinfunction "VCC_4") (pintype "passive"))
    )
    (net (code "80") (name "Net-(D1-~{H}IBUS)") (class "Default")
      (node (ref "D1") (pin "16") (pinfunction "~{H}IBUS_16") (pintype "passive"))
      (node (ref "R30") (pin "2") (pinfunction "2_2") (pintype "passive"))
    )
    (net (code "81") (name "Net-(D2-VLCD)") (class "Default")
      (node (ref "C21") (pin "2") (pintype "passive"))
      (node (ref "C26") (pin "2") (pintype "passive"))
      (node (ref "D2") (pin "23") (pinfunction "VLCD_23") (pintype "passive"))
      (node (ref "R4") (pin "2") (pintype "passive"))
    )
    (net (code "82") (name "Net-(HL2-PadK)") (class "Default")
      (node (ref "HL2") (pin "K") (pintype "passive"))
      (node (ref "R10") (pin "2") (pintype "passive"))
    )
    (net (code "83") (name "Net-(R10-Pad1)") (class "Default")
      (node (ref "R10") (pin "1") (pintype "passive"))
      (node (ref "V1") (pin "D") (pinfunction "D_D") (pintype "input"))
    )
    (net (code "84") (name "Net-(R17-Pad2)") (class "Default")
      (node (ref "R17") (pin "2") (pintype "passive"))
      (node (ref "R9") (pin "2") (pintype "passive"))
      (node (ref "V1") (pin "G") (pinfunction "G_G") (pintype "input"))
    )
    (net (code "85") (name "Net-(R56-Pad1)") (class "Default")
      (node (ref "R56") (pin "1") (pintype "passive"))
      (node (ref "V2") (pin "B") (pintype "passive"))
    )
    (net (code "86") (name "Net-(U5-PIO0_2{slash}FC0_CTS_SDA_SSEL0{slash}FC3_SSEL3{slash}CT32B2_CAP1)") (class "Default")
      (node (ref "R25") (pin "2") (pinfunction "2_2") (pintype "passive"))
      (node (ref "U5") (pin "36") (pinfunction "PIO0_2/FC0_CTS_SDA_SSEL0/FC3_SSEL3/CT32B2_CAP1_36") (pintype "passive"))
    )
    (net (code "87") (name "Net-(U5-VDDA)") (class "Default")
      (node (ref "C18") (pin "1") (pinfunction "1_1") (pintype "passive"))
      (node (ref "C19") (pin "1") (pinfunction "1_1") (pintype "passive"))
      (node (ref "FB3") (pin "1") (pinfunction "1_1") (pintype "passive"))
      (node (ref "U5") (pin "22") (pinfunction "VREFP_22") (pintype "passive"))
      (node (ref "U5") (pin "23") (pinfunction "VDDA_23") (pintype "passive"))
    )
    (net (code "88") (name "Net-(U5-VREFN)") (class "Default")
      (node (ref "C18") (pin "2") (pinfunction "2_2") (pintype "passive"))
      (node (ref "C19") (pin "2") (pinfunction "2_2") (pintype "passive"))
      (node (ref "FB2") (pin "2") (pinfunction "2_2") (pintype "passive"))
      (node (ref "U5") (pin "20") (pinfunction "VSSA_20") (pintype "passive"))
      (node (ref "U5") (pin "21") (pinfunction "VREFN_21") (pintype "passive"))
    )
    (net (code "89") (name "VBUS_T") (class "Default")
      (node (ref "R29") (pin "2") (pinfunction "2_2") (pintype "passive"))
      (node (ref "U5") (pin "26") (pinfunction "PIO1_6/ADC0_9/I/O_FC7_SCK/CT32B1_CAP2/I_USB_VBUS_26") (pintype "passive"))
    )
    (net (code "90") (name "unconnected-(D3-NC-Pad3)") (class "Default")
      (node (ref "D3") (pin "3") (pinfunction "NC_3") (pintype "passive"))
    )
    (net (code "91") (name "unconnected-(D3-NC-Pad4)") (class "Default")
      (node (ref "D3") (pin "4") (pinfunction "NC_4") (pintype "passive"))
    )
    (net (code "92") (name "unconnected-(U5-PIO0_3{slash}FC0_RTS_SCL_SSEL1{slash}FC2_SSEL2{slash}CT32B1_MAT3-Pad37)") (class "Default")
      (node (ref "U5") (pin "37") (pinfunction "PIO0_3/FC0_RTS_SCL_SSEL1/FC2_SSEL2/CT32B1_MAT3_37") (pintype "passive"))
    )
    (net (code "93") (name "unconnected-(U5-PIO0_5{slash}FC6_RXD_SDA_MOSI_DATA{slash}SCT0_OUT6{slash}CT32B0_MAT0-Pad39)") (class "Default")
      (node (ref "U5") (pin "39") (pinfunction "PIO0_5/FC6_RXD_SDA_MOSI_DATA/SCT0_OUT6/CT32B0_MAT0_39") (pintype "passive"))
    )
    (net (code "94") (name "unconnected-(U5-PIO0_11{slash}FC3_SCK{slash}FC6_RXD_SDA_MOSI_DATA{slash}CT32B2_MAT1-Pad46)") (class "Default")
      (node (ref "U5") (pin "46") (pinfunction "PIO0_11/FC3_SCK/FC6_RXD_SDA_MOSI_DATA/CT32B2_MAT1_46") (pintype "passive"))
    )
    (net (code "95") (name "unconnected-(U5-PIO0_12{slash}FC3_RXD_SDA_MOSI{slash}FC6_TXD_SCL_MISO_WS{slash}CT32B2_MAT3-Pad47)") (class "Default")
      (node (ref "U5") (pin "47") (pinfunction "PIO0_12/FC3_RXD_SDA_MOSI/FC6_TXD_SCL_MISO_WS/CT32B2_MAT3_47") (pintype "passive"))
    )
    (net (code "96") (name "unconnected-(U5-PIO0_13{slash}FC3_TXD_SCL_MISO{slash}SCT0_OUT4{slash}CT32B2_MAT0-Pad48)") (class "Default")
      (node (ref "U5") (pin "48") (pinfunction "PIO0_13/FC3_TXD_SCL_MISO/SCT0_OUT4/CT32B2_MAT0_48") (pintype "passive"))
    )
    (net (code "97") (name "unconnected-(U5-PIO0_14{slash}TCK{slash}FC3_CTS_SDA_SSEL0{slash}SCT0_OUT5{slash}CT32B2_MAT1{slash}FC1_SCK-Pad49)") (class "Default")
      (node (ref "U5") (pin "49") (pinfunction "PIO0_14/TCK/FC3_CTS_SDA_SSEL0/SCT0_OUT5/CT32B2_MAT1/FC1_SCK_49") (pintype "passive"))
    )
    (net (code "98") (name "unconnected-(U5-PIO0_25{slash}FC4_RTS_SCL_SSEL1{slash}FC6_CTS_SDA_SSEL0{slash}CT32B0_CAP2{slash}CT32B1_CAP1-Pad3)") (class "Default")
      (node (ref "U5") (pin "3") (pinfunction "PIO0_25/FC4_RTS_SCL_SSEL1/FC6_CTS_SDA_SSEL0/CT32B0_CAP2/CT32B1_CAP1_3") (pintype "passive"))
    )
    (net (code "99") (name "unconnected-(U5-PIO1_0{slash}ADC0_3{slash}PDM0_DATA{slash}FC2_RTS_SCL_SSEL1{slash}CT32B3_MAT1{slash}CT32B0_CAP0-Pad14)") (class "Default")
      (node (ref "U5") (pin "14") (pinfunction "PIO1_0/ADC0_3/PDM0_DATA/FC2_RTS_SCL_SSEL1/CT32B3_MAT1/CT32B0_CAP0_14") (pintype "passive"))
    )
    (net (code "100") (name "unconnected-(U5-PIO1_3{slash}ADC0_6{slash}FC7_SSEL2{slash}SCT0_OUT6{slash}FC3_SCK{slash}CT32B0_CAP1{slash}USB_UP_LED-Pad17)") (class "Default")
      (node (ref "U5") (pin "17") (pinfunction "PIO1_3/ADC0_6/FC7_SSEL2/SCT0_OUT6/FC3_SCK/CT32B0_CAP1/USB_UP_LED_17") (pintype "passive"))
    )
    (net (code "101") (name "unconnected-(U5-PIO1_4{slash}ADC0_7{slash}PDM1_CLK{slash}FC7_RTS_SCL_SSEL1{slash}SCT0_OUT7{slash}FC3_TXD_SCL_MISO{slash}CT32B0_MAT1-Pad18)") (class "Default")
      (node (ref "U5") (pin "18") (pinfunction "PIO1_4/ADC0_7/PDM1_CLK/FC7_RTS_SCL_SSEL1/SCT0_OUT7/FC3_TXD_SCL_MISO/CT32B0_MAT1_18") (pintype "passive"))
    )
    (net (code "102") (name "unconnected-(U5-PIO1_5{slash}ADC0_8{slash}PDM1_DATA{slash}FC7_CTS_SDA_SSEL0{slash}CT32B1_CAP0{slash}CT32B1_MAT3{slash}USB_FRAME-Pad19)") (class "Default")
      (node (ref "U5") (pin "19") (pinfunction "PIO1_5/ADC0_8/PDM1_DATA/FC7_CTS_SDA_SSEL0/CT32B1_CAP0/CT32B1_MAT3/USB_FRAME_19") (pintype "passive"))
    )
    (net (code "103") (name "unconnected-(U5-PIO1_7{slash}ADC0_10{slash}FC7_RXD_SDA_MOSI_DATA_{slash}CT32B1_MAT2{slash}CT32B1_CAP2-Pad27)") (class "Default")
      (node (ref "U5") (pin "27") (pinfunction "PIO1_7/ADC0_10/FC7_RXD_SDA_MOSI_DATA_/CT32B1_MAT2/CT32B1_CAP2_27") (pintype "passive"))
    )
    (net (code "104") (name "unconnected-(U5-PIO1_13{slash}FC5_TXD_SCL_MISO{slash}CT32B1_MAT1{slash}FC7_RXD_SDA_MOSI_DATA-Pad54)") (class "Default")
      (node (ref "U5") (pin "54") (pinfunction "PIO1_13/FC5_TXD_SCL_MISO/CT32B1_MAT1/FC7_RXD_SDA_MOSI_DATA_54") (pintype "passive"))
    )
    (net (code "105") (name "unconnected-(U5-PIO1_15{slash}PDM0_CLK{slash}SCT0_OUT5{slash}CT32B1_CAP3{slash}FC7_CTS_SDA_SSEL0-Pad62)") (class "Default")
      (node (ref "U5") (pin "62") (pinfunction "PIO1_15/PDM0_CLK/SCT0_OUT5/CT32B1_CAP3/FC7_CTS_SDA_SSEL0_62") (pintype "passive"))
    )
    (net (code "106") (name "unconnected-(U5-PIO1_16{slash}PDM0_DATA{slash}CT32B0_MAT0{slash}CT32B0_CAP0{slash}FC7_RTS_SCL_SSEL1-Pad7)") (class "Default")
      (node (ref "U5") (pin "7") (pinfunction "PIO1_16/PDM0_DATA/CT32B0_MAT0/CT32B0_CAP0/FC7_RTS_SCL_SSEL1_7") (pintype "passive"))
    )
    (net (code "107") (name "unconnected-(U5-PIO1_17{slash}MCLK{slash}UTICK_CAP3-Pad10)") (class "Default")
      (node (ref "U5") (pin "10") (pinfunction "PIO1_17/MCLK/UTICK_CAP3_10") (pintype "passive"))
    )
    (net (code "108") (name "unconnected-(U5-RTCXIN-Pad33)") (class "Default")
      (node (ref "U5") (pin "33") (pinfunction "RTCXIN_33") (pintype "passive"))
    )
    (net (code "109") (name "unconnected-(U5-RTCXOUT-Pad35)") (class "Default")
      (node (ref "U5") (pin "35") (pinfunction "RTCXOUT_35") (pintype "passive"))
    )
    (net (code "110") (name "unconnected-(U5-USB_DM-Pad6)") (class "Default")
      (node (ref "U5") (pin "6") (pinfunction "USB_DM_6") (pintype "passive"))
    )
    (net (code "111") (name "unconnected-(U5-USB_DP-Pad5)") (class "Default")
      (node (ref "U5") (pin "5") (pinfunction "USB_DP_5") (pintype "passive"))
    )
  )
)
